# Unified_Interface.net
KiCad netlist of a schematic drawn in Altium Designer
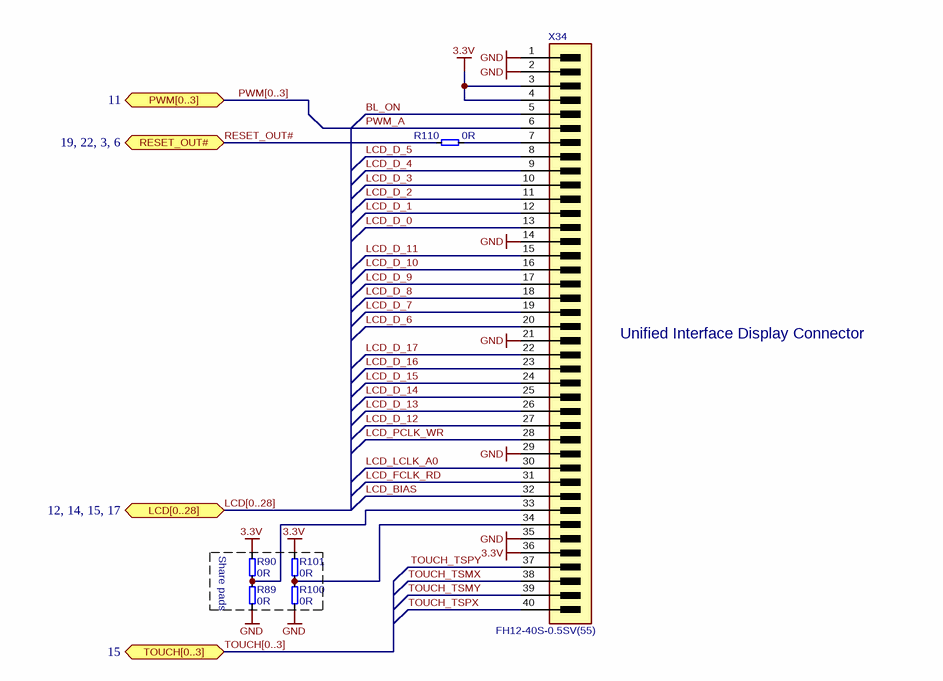
[diagram p0: Unified_Interface.SchDoc]

(export (version "E")
  (design (tool "Eeschema 10.0.6"))
  (components
    (comp (ref "R89")
      (value "0R")
      (footprint "T_RESC0603X30N")
      (description "Resistor 0 ohm 63mW 1% 0603")
      (fields (field (name "TOLERANCE") "1%"))
      (libsource (lib "Evaluation Board") (part "R-0R-63mW-1%-0603"))
    )
    (comp (ref "R90")
      (value "0R")
      (footprint "T_RESC0603X30N")
      (description "Resistor 0 ohm 63mW 1% 0603")
      (fields (field (name "TOLERANCE") "1%"))
      (libsource (lib "Evaluation Board") (part "R-0R-63mW-1%-0603"))
    )
    (comp (ref "R100")
      (value "0R")
      (footprint "T_RESC0603X30N")
      (description "Resistor 0 ohm 63mW 1% 0603")
      (fields (field (name "TOLERANCE") "1%"))
      (libsource (lib "Evaluation Board") (part "R-0R-63mW-1%-0603"))
    )
    (comp (ref "R101")
      (value "0R")
      (footprint "T_RESC0603X30N")
      (description "Resistor 0 ohm 63mW 1% 0603")
      (fields (field (name "TOLERANCE") "1%"))
      (libsource (lib "Evaluation Board") (part "R-0R-63mW-1%-0603"))
    )
    (comp (ref "R110")
      (value "0R")
      (footprint "T_RESC0603X30N")
      (description "Resistor 0 ohm 63mW 1% 0603")
      (fields (field (name "TOLERANCE") "1%"))
      (libsource (lib "Evaluation Board") (part "R-0R-63mW-1%-0603"))
    )
    (comp (ref "X34")
      (value "FH12-40S-0.5SV(55)")
      (footprint "T_Hirose_FH12-40S-0.5SV(55)")
      (description "0.50mm Pitch FFC/FPC Vertical RGB connector")
      (fields (field (name "MANUFACTURER PART NO.") "FH12-40S-0.5SV(55)"))
      (libsource (lib "Evaluation Board") (part "CON-Hirose-FH12-40S-0.5SV(55)-0.5mm"))
    )
  )
  (nets
    (net (code "38") (name "/BL_ON") (class "Default")
      (node (ref "X34") (pin "5") (pinfunction "PWCTRL_5") (pintype "passive"))
    )
    (net (code "40") (name "/LCD_BIAS") (class "Default")
      (node (ref "X34") (pin "32") (pinfunction "ENB_32") (pintype "passive"))
    )
    (net (code "41") (name "/LCD_D_0") (class "Default")
      (node (ref "X34") (pin "13") (pinfunction "B0_13") (pintype "passive"))
    )
    (net (code "42") (name "/LCD_D_1") (class "Default")
      (node (ref "X34") (pin "12") (pinfunction "B1_12") (pintype "passive"))
    )
    (net (code "43") (name "/LCD_D_2") (class "Default")
      (node (ref "X34") (pin "11") (pinfunction "B2_11") (pintype "passive"))
    )
    (net (code "44") (name "/LCD_D_3") (class "Default")
      (node (ref "X34") (pin "10") (pinfunction "B3_10") (pintype "passive"))
    )
    (net (code "45") (name "/LCD_D_4") (class "Default")
      (node (ref "X34") (pin "9") (pinfunction "B4_9") (pintype "passive"))
    )
    (net (code "46") (name "/LCD_D_5") (class "Default")
      (node (ref "X34") (pin "8") (pinfunction "B5_8") (pintype "passive"))
    )
    (net (code "47") (name "/LCD_D_6") (class "Default")
      (node (ref "X34") (pin "20") (pinfunction "G0_20") (pintype "passive"))
    )
    (net (code "48") (name "/LCD_D_7") (class "Default")
      (node (ref "X34") (pin "19") (pinfunction "G1_19") (pintype "passive"))
    )
    (net (code "49") (name "/LCD_D_8") (class "Default")
      (node (ref "X34") (pin "18") (pinfunction "G2_18") (pintype "passive"))
    )
    (net (code "50") (name "/LCD_D_9") (class "Default")
      (node (ref "X34") (pin "17") (pinfunction "G3_17") (pintype "passive"))
    )
    (net (code "51") (name "/LCD_D_10") (class "Default")
      (node (ref "X34") (pin "16") (pinfunction "G4_16") (pintype "passive"))
    )
    (net (code "52") (name "/LCD_D_11") (class "Default")
      (node (ref "X34") (pin "15") (pinfunction "G5_15") (pintype "passive"))
    )
    (net (code "53") (name "/LCD_D_12") (class "Default")
      (node (ref "X34") (pin "27") (pinfunction "R0_27") (pintype "passive"))
    )
    (net (code "54") (name "/LCD_D_13") (class "Default")
      (node (ref "X34") (pin "26") (pinfunction "R1_26") (pintype "passive"))
    )
    (net (code "55") (name "/LCD_D_14") (class "Default")
      (node (ref "X34") (pin "25") (pinfunction "R2_25") (pintype "passive"))
    )
    (net (code "56") (name "/LCD_D_15") (class "Default")
      (node (ref "X34") (pin "24") (pinfunction "R3_24") (pintype "passive"))
    )
    (net (code "57") (name "/LCD_D_16") (class "Default")
      (node (ref "X34") (pin "23") (pinfunction "R4_23") (pintype "passive"))
    )
    (net (code "58") (name "/LCD_D_17") (class "Default")
      (node (ref "X34") (pin "22") (pinfunction "R5_22") (pintype "passive"))
    )
    (net (code "59") (name "/LCD_FCLK_RD") (class "Default")
      (node (ref "X34") (pin "31") (pinfunction "VSYNC_31") (pintype "passive"))
    )
    (net (code "60") (name "/LCD_LCLK_A0") (class "Default")
      (node (ref "X34") (pin "30") (pinfunction "HSYNC_30") (pintype "passive"))
    )
    (net (code "61") (name "/LCD_PCLK_WR") (class "Default")
      (node (ref "X34") (pin "28") (pinfunction "DCLK_28") (pintype "passive"))
    )
    (net (code "63") (name "/PWM_A") (class "Default")
      (node (ref "X34") (pin "6") (pinfunction "LEDCTRL_6") (pintype "passive"))
    )
    (net (code "64") (name "/RESET_OUT#") (class "Default")
      (node (ref "R110") (pin "1") (pinfunction "1_1") (pintype "passive"))
    )
    (net (code "66") (name "/TOUCH_TSMX") (class "Default")
      (node (ref "X34") (pin "38") (pinfunction "XR_38") (pintype "passive"))
    )
    (net (code "67") (name "/TOUCH_TSMY") (class "Default")
      (node (ref "X34") (pin "39") (pinfunction "YD_39") (pintype "passive"))
    )
    (net (code "68") (name "/TOUCH_TSPX") (class "Default")
      (node (ref "X34") (pin "40") (pinfunction "XL_40") (pintype "passive"))
    )
    (net (code "69") (name "/TOUCH_TSPY") (class "Default")
      (node (ref "X34") (pin "37") (pinfunction "YU_37") (pintype "passive"))
    )
    (net (code "70") (name "3.3V") (class "Default")
      (node (ref "R101") (pin "2") (pinfunction "2_2") (pintype "passive"))
      (node (ref "R90") (pin "1") (pinfunction "1_1") (pintype "passive"))
      (node (ref "X34") (pin "3") (pinfunction "VCC_3") (pintype "power_in"))
      (node (ref "X34") (pin "36") (pinfunction "VDD_36") (pintype "passive"))
      (node (ref "X34") (pin "4") (pinfunction "VCC_4") (pintype "power_in"))
    )
    (net (code "71") (name "GND") (class "Default")
      (node (ref "R100") (pin "2") (pinfunction "2_2") (pintype "passive"))
      (node (ref "R89") (pin "2") (pinfunction "2_2") (pintype "passive"))
      (node (ref "X34") (pin "1") (pinfunction "VSS_1") (pintype "power_in"))
      (node (ref "X34") (pin "14") (pinfunction "VSS_14") (pintype "passive"))
      (node (ref "X34") (pin "2") (pinfunction "VSS_2") (pintype "power_in"))
      (node (ref "X34") (pin "21") (pinfunction "VSS_21") (pintype "passive"))
      (node (ref "X34") (pin "29") (pinfunction "VSS_29") (pintype "passive"))
      (node (ref "X34") (pin "35") (pinfunction "VSS_35") (pintype "passive"))
    )
    (net (code "72") (name "Net-(X34-NC)") (class "Default")
      (node (ref "R89") (pin "1") (pinfunction "1_1") (pintype "passive"))
      (node (ref "R90") (pin "2") (pinfunction "2_2") (pintype "passive"))
      (node (ref "X34") (pin "33") (pinfunction "NC_33") (pintype "passive"))
    )
    (net (code "73") (name "Net-(X34-RESET#)") (class "Default")
      (node (ref "R110") (pin "2") (pinfunction "2_2") (pintype "passive"))
      (node (ref "X34") (pin "7") (pinfunction "RESET#_7") (pintype "passive"))
    )
    (net (code "74") (name "Net-(X34-SHUT)") (class "Default")
      (node (ref "R100") (pin "1") (pinfunction "1_1") (pintype "passive"))
      (node (ref "R101") (pin "1") (pinfunction "1_1") (pintype "passive"))
      (node (ref "X34") (pin "34") (pinfunction "SHUT_34") (pintype "passive"))
    )
  )
)
